# RTD_100R_VDiv.net
KiCad netlist of a schematic drawn in Altium Designer
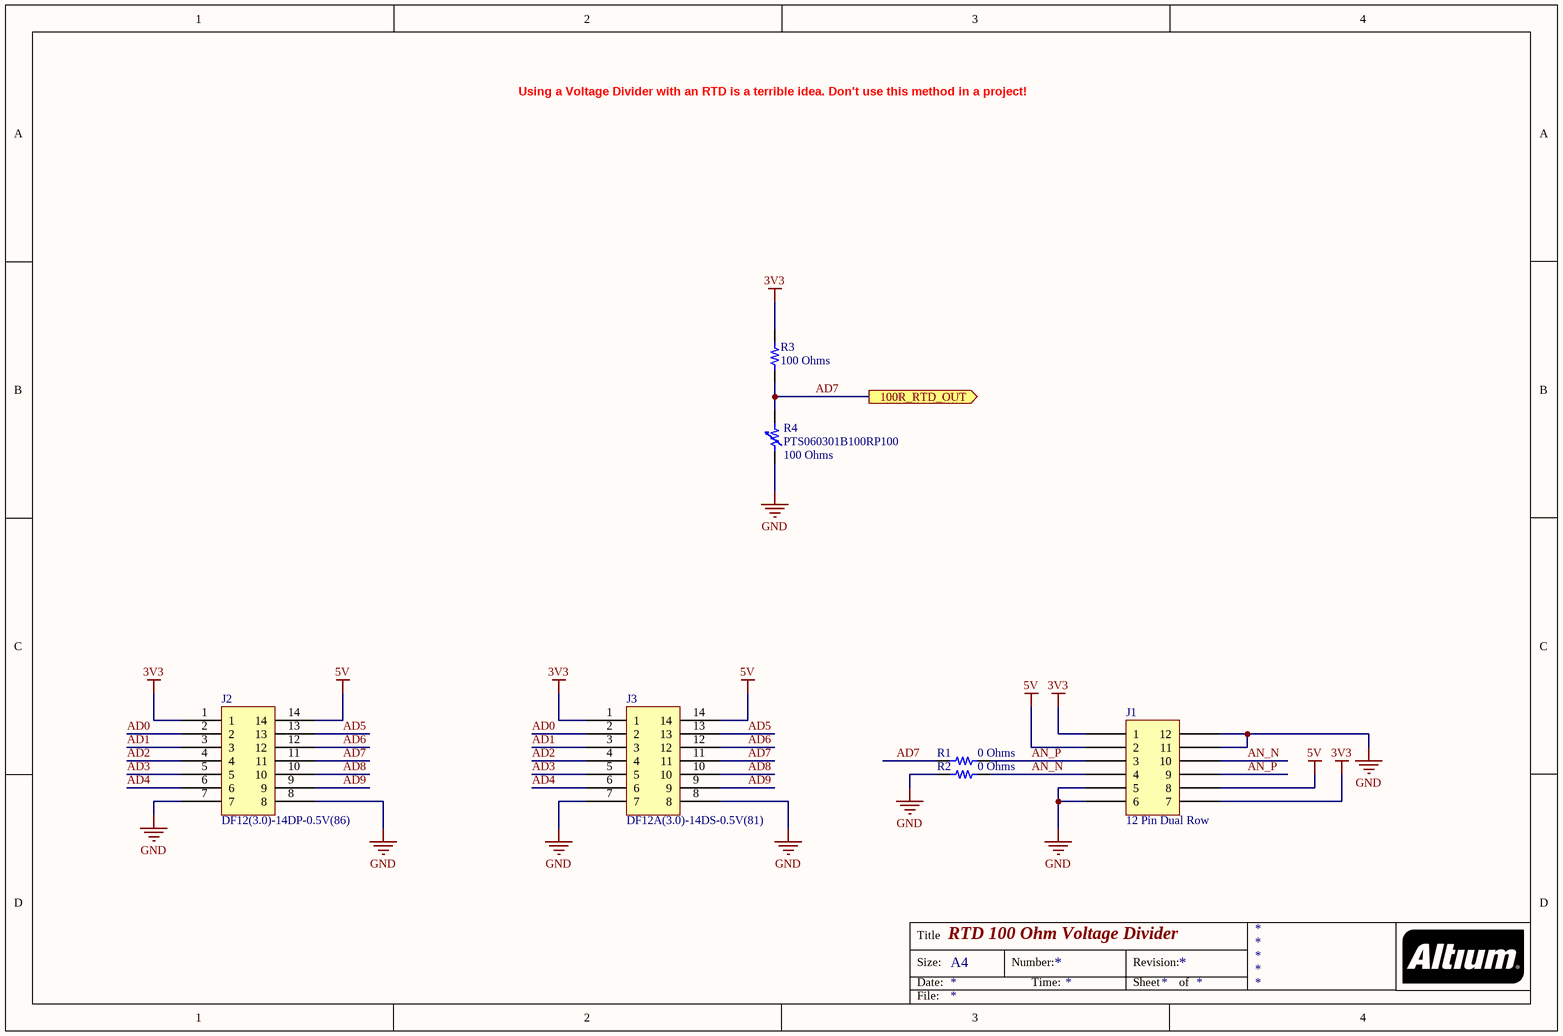
[diagram p0: RTD 100R VDiv.SchDoc]

(export (version "E")
  (design (tool "Eeschema 10.0.6"))
  (components
    (comp (ref "J1")
      (value "12 Pin Dual Row")
      (footprint "TE 5650118-3 Card Edge")
      (libsource (lib "CelestialUseful") (part "12 Pin Dual Row"))
    )
    (comp (ref "J2")
      (value "DF12(3.0)-14DP-0.5V(86)")
      (footprint "HIROSE DF12 3.0-14DP-0.5V 86")
      (description "CONN HDR 14POS SMD GOLD")
      (fields (field (name "MANUFACTURER") "Hirose Electric Co Ltd"))
      (libsource (lib "altiumlibrary.com") (part "14 Pin Dual Row"))
    )
    (comp (ref "J3")
      (value "DF12A(3.0)-14DS-0.5V(81)")
      (footprint "HIROSE DF12A 3.0-14DS-0.5V 81")
      (description "CONN RCPT 14POS SMD GOLD")
      (fields (field (name "MANUFACTURER") "Hirose Electric Co Ltd"))
      (libsource (lib "altiumlibrary.com") (part "14 Pin Dual Row"))
    )
    (comp (ref "R1")
      (value "0 Ohms")
      (footprint "RES 0603_1608")
      (description "RES SMD 0 OHM JUMPER 1/10W 0603")
      (fields
        (field (name "PART NUMBER") "ERJ-3GEY0R00V")
        (field (name "MANUFACTURER") "Panasonic Electronic Components")
      )
      (libsource (lib "altiumlibrary.com") (part "Resistor"))
    )
    (comp (ref "R2")
      (value "0 Ohms")
      (footprint "RES 0603_1608")
      (description "RES SMD 0 OHM JUMPER 1/10W 0603")
      (fields
        (field (name "PART NUMBER") "ERJ-3GEY0R00V")
        (field (name "MANUFACTURER") "Panasonic Electronic Components")
      )
      (libsource (lib "altiumlibrary.com") (part "Resistor"))
    )
    (comp (ref "R3")
      (value "100 Ohms")
      (footprint "RES 0603_1608")
      (description "RES SMD 100 OHM 1% 1/10W 0603")
      (fields
        (field (name "PART NUMBER") "ERJ-3EKF1000V")
        (field (name "MANUFACTURER") "Panasonic Electronic Components")
      )
      (libsource (lib "altiumlibrary.com") (part "Resistor"))
    )
    (comp (ref "R4")
      (value "PTS060301B100RP100")
      (footprint "RTD 0603_1608")
      (description "SENSOR RTD 100OHM 1% 0603")
      (fields (field (name "MANUFACTURER") "Vishay Beyschlag") (field (name "RESISTANCE @ 0°C") "100 Ohms"))
      (libsource (lib "altiumlibrary.com") (part "RTD"))
    )
  )
  (nets
    (net (code "1") (name "/AD0") (class "Default")
      (node (ref "J2") (pin "2") (pinfunction "2_2") (pintype "passive"))
      (node (ref "J3") (pin "2") (pinfunction "2_2") (pintype "passive"))
    )
    (net (code "2") (name "/AD1") (class "Default")
      (node (ref "J2") (pin "3") (pinfunction "3_3") (pintype "passive"))
      (node (ref "J3") (pin "3") (pinfunction "3_3") (pintype "passive"))
    )
    (net (code "3") (name "/AD2") (class "Default")
      (node (ref "J2") (pin "4") (pinfunction "4_4") (pintype "passive"))
      (node (ref "J3") (pin "4") (pinfunction "4_4") (pintype "passive"))
    )
    (net (code "4") (name "/AD3") (class "Default")
      (node (ref "J2") (pin "5") (pinfunction "5_5") (pintype "passive"))
      (node (ref "J3") (pin "5") (pinfunction "5_5") (pintype "passive"))
    )
    (net (code "5") (name "/AD4") (class "Default")
      (node (ref "J2") (pin "6") (pinfunction "6_6") (pintype "passive"))
      (node (ref "J3") (pin "6") (pinfunction "6_6") (pintype "passive"))
    )
    (net (code "6") (name "/AD5") (class "Default")
      (node (ref "J2") (pin "13") (pinfunction "13_13") (pintype "passive"))
      (node (ref "J3") (pin "13") (pinfunction "13_13") (pintype "passive"))
    )
    (net (code "7") (name "/AD6") (class "Default")
      (node (ref "J2") (pin "12") (pinfunction "12_12") (pintype "passive"))
      (node (ref "J3") (pin "12") (pinfunction "12_12") (pintype "passive"))
    )
    (net (code "8") (name "/AD7") (class "Default")
      (node (ref "J2") (pin "11") (pinfunction "11_11") (pintype "passive"))
      (node (ref "J3") (pin "11") (pinfunction "11_11") (pintype "passive"))
      (node (ref "R1") (pin "1") (pinfunction "1_1") (pintype "passive"))
      (node (ref "R3") (pin "1") (pinfunction "1_1") (pintype "passive"))
      (node (ref "R4") (pin "2") (pinfunction "2_2") (pintype "passive"))
    )
    (net (code "9") (name "/AD8") (class "Default")
      (node (ref "J2") (pin "10") (pinfunction "10_10") (pintype "passive"))
      (node (ref "J3") (pin "10") (pinfunction "10_10") (pintype "passive"))
    )
    (net (code "10") (name "/AD9") (class "Default")
      (node (ref "J2") (pin "9") (pinfunction "9_9") (pintype "passive"))
      (node (ref "J3") (pin "9") (pinfunction "9_9") (pintype "passive"))
    )
    (net (code "11") (name "/AN_N") (class "Default")
      (node (ref "J1") (pin "10") (pinfunction "10_10") (pintype "passive"))
      (node (ref "J1") (pin "4") (pinfunction "4_4") (pintype "passive"))
      (node (ref "R2") (pin "2") (pinfunction "2_2") (pintype "passive"))
    )
    (net (code "12") (name "/AN_P") (class "Default")
      (node (ref "J1") (pin "3") (pinfunction "3_3") (pintype "passive"))
      (node (ref "J1") (pin "9") (pinfunction "9_9") (pintype "passive"))
      (node (ref "R1") (pin "2") (pinfunction "2_2") (pintype "passive"))
    )
    (net (code "13") (name "3V3") (class "Default")
      (node (ref "J1") (pin "1") (pinfunction "1_1") (pintype "passive"))
      (node (ref "J1") (pin "7") (pinfunction "7_7") (pintype "passive"))
      (node (ref "J2") (pin "1") (pinfunction "1_1") (pintype "passive"))
      (node (ref "J3") (pin "1") (pinfunction "1_1") (pintype "passive"))
      (node (ref "R3") (pin "2") (pinfunction "2_2") (pintype "passive"))
    )
    (net (code "14") (name "5V") (class "Default")
      (node (ref "J1") (pin "2") (pinfunction "2_2") (pintype "passive"))
      (node (ref "J1") (pin "8") (pinfunction "8_8") (pintype "passive"))
      (node (ref "J2") (pin "14") (pinfunction "14_14") (pintype "passive"))
      (node (ref "J3") (pin "14") (pinfunction "14_14") (pintype "passive"))
    )
    (net (code "15") (name "GND") (class "Default")
      (node (ref "J1") (pin "11") (pinfunction "11_11") (pintype "passive"))
      (node (ref "J1") (pin "12") (pinfunction "12_12") (pintype "passive"))
      (node (ref "J1") (pin "5") (pinfunction "5_5") (pintype "passive"))
      (node (ref "J1") (pin "6") (pinfunction "6_6") (pintype "passive"))
      (node (ref "J2") (pin "7") (pinfunction "7_7") (pintype "passive"))
      (node (ref "J2") (pin "8") (pinfunction "8_8") (pintype "passive"))
      (node (ref "J3") (pin "7") (pinfunction "7_7") (pintype "passive"))
      (node (ref "J3") (pin "8") (pinfunction "8_8") (pintype "passive"))
      (node (ref "R2") (pin "1") (pinfunction "1_1") (pintype "passive"))
      (node (ref "R4") (pin "1") (pinfunction "1_1") (pintype "passive"))
    )
  )
)
